# MSP_IOboard.net
KiCad netlist of a schematic drawn in Altium Designer
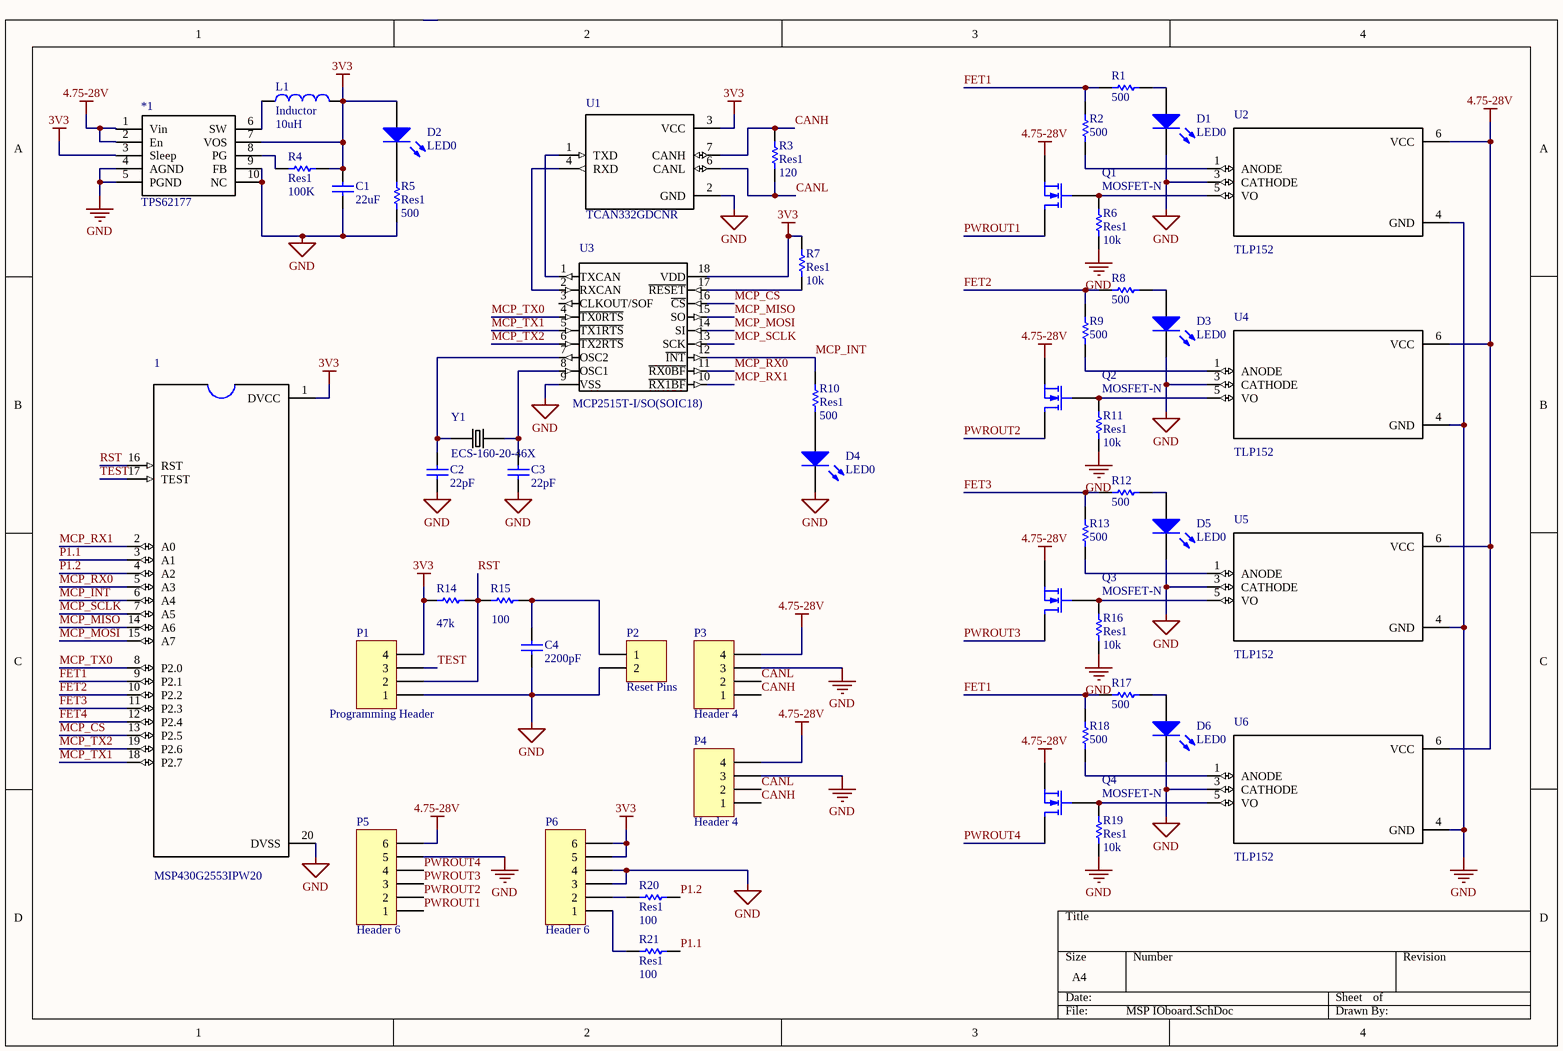
[diagram p0: MSP IOboard.SchDoc]

(export (version "E")
  (design (tool "Eeschema 10.0.6"))
  (components
    (comp (ref "*1")
      (value "TPS62177")
      (footprint "SON80P400X400X80-10N")
      (libsource (lib "SON80P400X400X80-10N") (part "TPS62177"))
    )
    (comp (ref "1")
      (value "MSP430G2553IPW20")
      (footprint "TSSOP-20")
      (description "MSP430G2x53, MSP430G2x13 Mixed Signal Microcontroller 20-TSSOP -40 to 85")
      (fields (field (name "MF") "Texas Instruments"))
      (libsource (lib "MSP430G2553IPW20") (part "MSP430G2553IPW20"))
    )
    (comp (ref "C1")
      (value "22uF")
      (footprint "0603")
      (description "Capacitor")
      (fields (field (name "Comment") "Cap") (field (name "PUBLISHER") "Altium Limited"))
      (libsource (lib "Miscellaneous Devices") (part "Cap"))
    )
    (comp (ref "C2")
      (value "22pF")
      (footprint "0603")
      (description "Capacitor")
      (fields (field (name "Comment") "Cap") (field (name "PUBLISHER") "Altium Limited"))
      (libsource (lib "Miscellaneous Devices") (part "Cap"))
    )
    (comp (ref "C3")
      (value "22pF")
      (footprint "0603")
      (description "Capacitor")
      (fields (field (name "Comment") "Cap") (field (name "PUBLISHER") "Altium Limited"))
      (libsource (lib "Miscellaneous Devices") (part "Cap"))
    )
    (comp (ref "C4")
      (value "2200pF")
      (footprint "0603")
      (description "Capacitor")
      (fields (field (name "Comment") "Cap") (field (name "PUBLISHER") "Altium Limited"))
      (libsource (lib "Miscellaneous Devices") (part "Cap"))
    )
    (comp (ref "D1")
      (value "LED0")
      (footprint "0603")
      (description "Typical INFRARED GaAs LED")
      (fields (field (name "PUBLISHER") "Altium Limited"))
      (libsource (lib "Miscellaneous Devices") (part "LED0"))
    )
    (comp (ref "D2")
      (value "LED0")
      (footprint "0603")
      (description "Typical INFRARED GaAs LED")
      (fields (field (name "PUBLISHER") "Altium Limited"))
      (libsource (lib "Miscellaneous Devices") (part "LED0"))
    )
    (comp (ref "D3")
      (value "LED0")
      (footprint "0603")
      (description "Typical INFRARED GaAs LED")
      (fields (field (name "PUBLISHER") "Altium Limited"))
      (libsource (lib "Miscellaneous Devices") (part "LED0"))
    )
    (comp (ref "D4")
      (value "LED0")
      (footprint "0603")
      (description "Typical INFRARED GaAs LED")
      (fields (field (name "PUBLISHER") "Altium Limited"))
      (libsource (lib "Miscellaneous Devices") (part "LED0"))
    )
    (comp (ref "D5")
      (value "LED0")
      (footprint "0603")
      (description "Typical INFRARED GaAs LED")
      (fields (field (name "PUBLISHER") "Altium Limited"))
      (libsource (lib "Miscellaneous Devices") (part "LED0"))
    )
    (comp (ref "D6")
      (value "LED0")
      (footprint "0603")
      (description "Typical INFRARED GaAs LED")
      (fields (field (name "PUBLISHER") "Altium Limited"))
      (libsource (lib "Miscellaneous Devices") (part "LED0"))
    )
    (comp (ref "L1")
      (value "Inductor")
      (footprint "INDC2520X18N")
      (fields (field (name "ALTIUM_VALUE") "10uH") (field (name "PUBLISHER") "Altium Limited"))
      (libsource (lib "Miscellaneous Devices") (part "Inductor"))
    )
    (comp (ref "P1")
      (value "Programming Header")
      (footprint "HDR1X4")
      (description "Header, 4-Pin")
      (fields (field (name "PUBLISHER") "Altium Limited"))
      (libsource (lib "Miscellaneous Connectors") (part "Header 4"))
    )
    (comp (ref "P2")
      (value "Reset Pins")
      (footprint "HDR1X2")
      (description "Header, 2-Pin")
      (fields (field (name "PUBLISHER") "Altium Limited"))
      (libsource (lib "Miscellaneous Connectors") (part "Header 2"))
    )
    (comp (ref "P3")
      (value "Header 4")
      (footprint "HDR1X4")
      (description "Header, 4-Pin")
      (fields (field (name "PUBLISHER") "Altium Limited"))
      (libsource (lib "Miscellaneous Connectors") (part "Header 4"))
    )
    (comp (ref "P4")
      (value "Header 4")
      (footprint "HDR1X4")
      (description "Header, 4-Pin")
      (fields (field (name "PUBLISHER") "Altium Limited"))
      (libsource (lib "Miscellaneous Connectors") (part "Header 4"))
    )
    (comp (ref "P5")
      (value "Header 6")
      (footprint "HDR1X6")
      (description "Header, 6-Pin")
      (fields (field (name "PUBLISHER") "Altium Limited"))
      (libsource (lib "Miscellaneous Connectors") (part "Header 6"))
    )
    (comp (ref "P6")
      (value "Header 6")
      (footprint "HDR1X6")
      (description "Header, 6-Pin")
      (fields (field (name "PUBLISHER") "Altium Limited"))
      (libsource (lib "Miscellaneous Connectors") (part "Header 6"))
    )
    (comp (ref "Q1")
      (value "MOSFET-N")
      (footprint "SOT95P230X110-3N")
      (description "N-Channel MOSFET")
      (fields (field (name "PUBLISHER") "Altium Limited"))
      (libsource (lib "Miscellaneous Devices") (part "MOSFET-N"))
    )
    (comp (ref "Q2")
      (value "MOSFET-N")
      (footprint "SOT95P230X110-3N")
      (description "N-Channel MOSFET")
      (fields (field (name "PUBLISHER") "Altium Limited"))
      (libsource (lib "Miscellaneous Devices") (part "MOSFET-N"))
    )
    (comp (ref "Q3")
      (value "MOSFET-N")
      (footprint "SOT95P230X110-3N")
      (description "N-Channel MOSFET")
      (fields (field (name "PUBLISHER") "Altium Limited"))
      (libsource (lib "Miscellaneous Devices") (part "MOSFET-N"))
    )
    (comp (ref "Q4")
      (value "MOSFET-N")
      (footprint "SOT95P230X110-3N")
      (description "N-Channel MOSFET")
      (fields (field (name "PUBLISHER") "Altium Limited"))
      (libsource (lib "Miscellaneous Devices") (part "MOSFET-N"))
    )
    (comp (ref "R1")
      (value "500")
      (footprint "RESC2012X70")
      (description "Resistor")
      (fields (field (name "Comment") "Res1") (field (name "PUBLISHER") "Altium Limited"))
      (libsource (lib "Miscellaneous Devices") (part "Res1"))
    )
    (comp (ref "R2")
      (value "500")
      (footprint "RESC2012X70")
      (description "Resistor")
      (fields (field (name "Comment") "Res1") (field (name "PUBLISHER") "Altium Limited"))
      (libsource (lib "Miscellaneous Devices") (part "Res1"))
    )
    (comp (ref "R3")
      (value "Res1")
      (footprint "AXIAL-0.3")
      (description "Resistor")
      (fields (field (name "ALTIUM_VALUE") "120") (field (name "PUBLISHER") "Altium Limited"))
      (libsource (lib "Miscellaneous Devices") (part "Res1"))
    )
    (comp (ref "R4")
      (value "Res1")
      (footprint "RESC2012X70")
      (description "Resistor")
      (fields (field (name "ALTIUM_VALUE") "100K") (field (name "PUBLISHER") "Altium Limited"))
      (libsource (lib "Miscellaneous Devices") (part "Res1"))
    )
    (comp (ref "R5")
      (value "Res1")
      (footprint "RESC2012X70")
      (description "Resistor")
      (fields (field (name "ALTIUM_VALUE") "500") (field (name "PUBLISHER") "Altium Limited"))
      (libsource (lib "Miscellaneous Devices") (part "Res1"))
    )
    (comp (ref "R6")
      (value "Res1")
      (footprint "RESC2012X70")
      (description "Resistor")
      (fields (field (name "ALTIUM_VALUE") "10k") (field (name "PUBLISHER") "Altium Limited"))
      (libsource (lib "Miscellaneous Devices") (part "Res1"))
    )
    (comp (ref "R7")
      (value "Res1")
      (footprint "RESC2012X70")
      (description "Resistor")
      (fields (field (name "ALTIUM_VALUE") "10k") (field (name "PUBLISHER") "Altium Limited"))
      (libsource (lib "Miscellaneous Devices") (part "Res1"))
    )
    (comp (ref "R8")
      (value "500")
      (footprint "RESC2012X70")
      (description "Resistor")
      (fields (field (name "Comment") "Res1") (field (name "PUBLISHER") "Altium Limited"))
      (libsource (lib "Miscellaneous Devices") (part "Res1"))
    )
    (comp (ref "R9")
      (value "500")
      (footprint "RESC2012X70")
      (description "Resistor")
      (fields (field (name "Comment") "Res1") (field (name "PUBLISHER") "Altium Limited"))
      (libsource (lib "Miscellaneous Devices") (part "Res1"))
    )
    (comp (ref "R10")
      (value "Res1")
      (footprint "RESC2012X70")
      (description "Resistor")
      (fields (field (name "ALTIUM_VALUE") "500") (field (name "PUBLISHER") "Altium Limited"))
      (libsource (lib "Miscellaneous Devices") (part "Res1"))
    )
    (comp (ref "R11")
      (value "Res1")
      (footprint "RESC2012X70")
      (description "Resistor")
      (fields (field (name "ALTIUM_VALUE") "10k") (field (name "PUBLISHER") "Altium Limited"))
      (libsource (lib "Miscellaneous Devices") (part "Res1"))
    )
    (comp (ref "R12")
      (value "500")
      (footprint "RESC2012X70")
      (description "Resistor")
      (fields (field (name "Comment") "Res1") (field (name "PUBLISHER") "Altium Limited"))
      (libsource (lib "Miscellaneous Devices") (part "Res1"))
    )
    (comp (ref "R13")
      (value "500")
      (footprint "RESC2012X70")
      (description "Resistor")
      (fields (field (name "Comment") "Res1") (field (name "PUBLISHER") "Altium Limited"))
      (libsource (lib "Miscellaneous Devices") (part "Res1"))
    )
    (comp (ref "R14")
      (value "47k")
      (footprint "RESC2012X70")
      (description "Resistor")
      (fields (field (name "Comment") "Res1") (field (name "PUBLISHER") "Altium Limited"))
      (libsource (lib "Miscellaneous Devices") (part "Res1"))
    )
    (comp (ref "R15")
      (value "100")
      (footprint "RESC2012X70")
      (description "Resistor")
      (fields (field (name "Comment") "Res1") (field (name "PUBLISHER") "Altium Limited"))
      (libsource (lib "Miscellaneous Devices") (part "Res1"))
    )
    (comp (ref "R16")
      (value "Res1")
      (footprint "RESC2012X70")
      (description "Resistor")
      (fields (field (name "ALTIUM_VALUE") "10k") (field (name "PUBLISHER") "Altium Limited"))
      (libsource (lib "Miscellaneous Devices") (part "Res1"))
    )
    (comp (ref "R17")
      (value "500")
      (footprint "RESC2012X70")
      (description "Resistor")
      (fields (field (name "Comment") "Res1") (field (name "PUBLISHER") "Altium Limited"))
      (libsource (lib "Miscellaneous Devices") (part "Res1"))
    )
    (comp (ref "R18")
      (value "500")
      (footprint "RESC2012X70")
      (description "Resistor")
      (fields (field (name "Comment") "Res1") (field (name "PUBLISHER") "Altium Limited"))
      (libsource (lib "Miscellaneous Devices") (part "Res1"))
    )
    (comp (ref "R19")
      (value "Res1")
      (footprint "RESC2012X70")
      (description "Resistor")
      (fields (field (name "ALTIUM_VALUE") "10k") (field (name "PUBLISHER") "Altium Limited"))
      (libsource (lib "Miscellaneous Devices") (part "Res1"))
    )
    (comp (ref "R20")
      (value "Res1")
      (footprint "RESC2012X70")
      (description "Resistor")
      (fields (field (name "ALTIUM_VALUE") "100") (field (name "PUBLISHER") "Altium Limited"))
      (libsource (lib "Miscellaneous Devices") (part "Res1"))
    )
    (comp (ref "R21")
      (value "Res1")
      (footprint "RESC2012X70")
      (description "Resistor")
      (fields (field (name "ALTIUM_VALUE") "100") (field (name "PUBLISHER") "Altium Limited"))
      (libsource (lib "Miscellaneous Devices") (part "Res1"))
    )
    (comp (ref "U1")
      (value "TCAN332GDCNR")
      (footprint "SOT65P280X145-8N")
      (description "3.3-V CAN Transceivers with CAN FD _Flexible Data Rate_ 8-SOT-23 -40 to 125")
      (fields (field (name "MF") "Texas Instruments"))
      (libsource (lib "TCAN332GDCNR") (part "TCAN332GDCNR"))
    )
    (comp (ref "U2")
      (value "TLP152")
      (footprint "SOIC127P375X700X220-5N")
      (description "Optocoupler, Gate Driver, 3.75kv, Smdip")
      (fields (field (name "MF") "Toshiba"))
      (libsource (lib "TLP152") (part "TLP152"))
    )
    (comp (ref "U3")
      (value "MCP2515T-I/SO(SOIC18)")
      (footprint "SOIC18-1.27-11.5X7.5MM")
      (description "MCP2515 Series 5.5 V 1 Mb/s Stand Alone SPI Interface CAN Controller- SOIC-18")
      (fields (field (name "MF") "Microchip") (field (name "MP") "MCP2515T-I/SO"))
      (libsource (lib "INTERFACE-MCP2515T-I_SO_SOIC18_") (part "INTERFACE-MCP2515T-I/SO(SOIC18)"))
    )
    (comp (ref "U4")
      (value "TLP152")
      (footprint "SOIC127P375X700X220-5N")
      (description "Optocoupler, Gate Driver, 3.75kv, Smdip")
      (fields (field (name "MF") "Toshiba"))
      (libsource (lib "TLP152") (part "TLP152"))
    )
    (comp (ref "U5")
      (value "TLP152")
      (footprint "SOIC127P375X700X220-5N")
      (description "Optocoupler, Gate Driver, 3.75kv, Smdip")
      (fields (field (name "MF") "Toshiba"))
      (libsource (lib "TLP152") (part "TLP152"))
    )
    (comp (ref "U6")
      (value "TLP152")
      (footprint "SOIC127P375X700X220-5N")
      (description "Optocoupler, Gate Driver, 3.75kv, Smdip")
      (fields (field (name "MF") "Toshiba"))
      (libsource (lib "TLP152") (part "TLP152"))
    )
    (comp (ref "Y1")
      (value "ECS-160-20-46X")
      (footprint "XTAL_ECS-160-20-46X")
      (description "Crystal 16MHz Â±30ppm _Tol_ Â±50ppm _Stability_ 20pF FUND 50Ohm")
      (fields (field (name "MF") "ECS Inc."))
      (libsource (lib "ECS-160-20-46X") (part "ECS-160-20-46X"))
    )
  )
  (nets
    (net (code "1") (name "/CANH") (class "Default")
      (node (ref "P3") (pin "1") (pinfunction "1_1") (pintype "passive"))
      (node (ref "P4") (pin "1") (pinfunction "1_1") (pintype "passive"))
      (node (ref "R3") (pin "2") (pinfunction "2_2") (pintype "passive"))
      (node (ref "U1") (pin "7") (pinfunction "CANH_7") (pintype "bidirectional"))
    )
    (net (code "2") (name "/CANL") (class "Default")
      (node (ref "P3") (pin "2") (pinfunction "2_2") (pintype "passive"))
      (node (ref "P4") (pin "2") (pinfunction "2_2") (pintype "passive"))
      (node (ref "R3") (pin "1") (pinfunction "1_1") (pintype "passive"))
      (node (ref "U1") (pin "6") (pinfunction "CANL_6") (pintype "bidirectional"))
    )
    (net (code "3") (name "/FET1") (class "Default")
      (node (ref "1") (pin "9") (pinfunction "P2.1_9") (pintype "bidirectional"))
      (node (ref "R1") (pin "1") (pinfunction "1_1") (pintype "passive"))
      (node (ref "R17") (pin "2") (pinfunction "2_2") (pintype "passive"))
      (node (ref "R18") (pin "1") (pinfunction "1_1") (pintype "passive"))
      (node (ref "R2") (pin "2") (pinfunction "2_2") (pintype "passive"))
    )
    (net (code "4") (name "/FET2") (class "Default")
      (node (ref "1") (pin "10") (pinfunction "P2.2_10") (pintype "bidirectional"))
      (node (ref "R8") (pin "1") (pinfunction "1_1") (pintype "passive"))
      (node (ref "R9") (pin "1") (pinfunction "1_1") (pintype "passive"))
    )
    (net (code "5") (name "/FET3") (class "Default")
      (node (ref "1") (pin "11") (pinfunction "P2.3_11") (pintype "bidirectional"))
      (node (ref "R12") (pin "2") (pinfunction "2_2") (pintype "passive"))
      (node (ref "R13") (pin "1") (pinfunction "1_1") (pintype "passive"))
    )
    (net (code "6") (name "/FET4") (class "Default")
      (node (ref "1") (pin "12") (pinfunction "P2.4_12") (pintype "bidirectional"))
    )
    (net (code "7") (name "/MCP_CS") (class "Default")
      (node (ref "1") (pin "13") (pinfunction "P2.5_13") (pintype "bidirectional"))
      (node (ref "U3") (pin "16") (pinfunction "~{CS}_16") (pintype "input"))
    )
    (net (code "8") (name "/MCP_INT") (class "Default")
      (node (ref "1") (pin "6") (pinfunction "A4_6") (pintype "bidirectional"))
      (node (ref "R10") (pin "2") (pinfunction "2_2") (pintype "passive"))
      (node (ref "U3") (pin "12") (pinfunction "~{INT}_12") (pintype "output"))
    )
    (net (code "9") (name "/MCP_MISO") (class "Default")
      (node (ref "1") (pin "14") (pinfunction "A6_14") (pintype "bidirectional"))
      (node (ref "U3") (pin "15") (pinfunction "SO_15") (pintype "output"))
    )
    (net (code "10") (name "/MCP_MOSI") (class "Default")
      (node (ref "1") (pin "15") (pinfunction "A7_15") (pintype "bidirectional"))
      (node (ref "U3") (pin "14") (pinfunction "SI_14") (pintype "input"))
    )
    (net (code "11") (name "/MCP_RX0") (class "Default")
      (node (ref "1") (pin "5") (pinfunction "A3_5") (pintype "bidirectional"))
      (node (ref "U3") (pin "11") (pinfunction "~{RX0BF}_11") (pintype "output"))
    )
    (net (code "12") (name "/MCP_RX1") (class "Default")
      (node (ref "1") (pin "2") (pinfunction "A0_2") (pintype "bidirectional"))
      (node (ref "U3") (pin "10") (pinfunction "~{RX1BF}_10") (pintype "output"))
    )
    (net (code "13") (name "/MCP_SCLK") (class "Default")
      (node (ref "1") (pin "7") (pinfunction "A5_7") (pintype "bidirectional"))
      (node (ref "U3") (pin "13") (pinfunction "SCK_13") (pintype "input"))
    )
    (net (code "14") (name "/MCP_TX0") (class "Default")
      (node (ref "1") (pin "8") (pinfunction "P2.0_8") (pintype "bidirectional"))
      (node (ref "U3") (pin "4") (pinfunction "~{TX0RTS}_4") (pintype "input"))
    )
    (net (code "15") (name "/MCP_TX1") (class "Default")
      (node (ref "1") (pin "18") (pinfunction "P2.7_18") (pintype "bidirectional"))
      (node (ref "U3") (pin "5") (pinfunction "~{TX1RTS}_5") (pintype "input"))
    )
    (net (code "16") (name "/MCP_TX2") (class "Default")
      (node (ref "1") (pin "19") (pinfunction "P2.6_19") (pintype "bidirectional"))
      (node (ref "U3") (pin "6") (pinfunction "~{TX2RTS}_6") (pintype "input"))
    )
    (net (code "17") (name "/P1.1") (class "Default")
      (node (ref "1") (pin "3") (pinfunction "A1_3") (pintype "bidirectional"))
      (node (ref "R21") (pin "1") (pinfunction "1_1") (pintype "passive"))
    )
    (net (code "18") (name "/P1.2") (class "Default")
      (node (ref "1") (pin "4") (pinfunction "A2_4") (pintype "bidirectional"))
      (node (ref "R20") (pin "1") (pinfunction "1_1") (pintype "passive"))
    )
    (net (code "19") (name "/PWROUT1") (class "Default")
      (node (ref "P5") (pin "1") (pinfunction "1_1") (pintype "passive"))
      (node (ref "Q1") (pin "1") (pinfunction "D_1") (pintype "passive"))
    )
    (net (code "20") (name "/PWROUT2") (class "Default")
      (node (ref "P5") (pin "2") (pinfunction "2_2") (pintype "passive"))
      (node (ref "Q2") (pin "1") (pinfunction "D_1") (pintype "passive"))
    )
    (net (code "21") (name "/PWROUT3") (class "Default")
      (node (ref "P5") (pin "3") (pinfunction "3_3") (pintype "passive"))
      (node (ref "Q3") (pin "1") (pinfunction "D_1") (pintype "passive"))
    )
    (net (code "22") (name "/PWROUT4") (class "Default")
      (node (ref "P5") (pin "4") (pinfunction "4_4") (pintype "passive"))
      (node (ref "Q4") (pin "1") (pinfunction "D_1") (pintype "passive"))
    )
    (net (code "23") (name "/RST") (class "Default")
      (node (ref "1") (pin "16") (pinfunction "RST_16") (pintype "input"))
      (node (ref "P1") (pin "2") (pinfunction "2_2") (pintype "passive"))
      (node (ref "R14") (pin "2") (pinfunction "2_2") (pintype "passive"))
      (node (ref "R15") (pin "1") (pinfunction "1_1") (pintype "passive"))
    )
    (net (code "24") (name "/TEST") (class "Default")
      (node (ref "1") (pin "17") (pinfunction "TEST_17") (pintype "input"))
      (node (ref "P1") (pin "3") (pinfunction "3_3") (pintype "passive"))
    )
    (net (code "25") (name "3V3") (class "Default")
      (node (ref "*1") (pin "3") (pinfunction "Sleep_3") (pintype "passive"))
      (node (ref "*1") (pin "7") (pinfunction "VOS_7") (pintype "passive"))
      (node (ref "1") (pin "1") (pinfunction "DVCC_1") (pintype "power_in"))
      (node (ref "C1") (pin "2") (pinfunction "2_2") (pintype "passive"))
      (node (ref "D2") (pin "1") (pinfunction "A_1") (pintype "passive"))
      (node (ref "L1") (pin "2") (pinfunction "2_2") (pintype "passive"))
      (node (ref "P1") (pin "4") (pinfunction "4_4") (pintype "passive"))
      (node (ref "P6") (pin "5") (pinfunction "5_5") (pintype "passive"))
      (node (ref "P6") (pin "6") (pinfunction "6_6") (pintype "passive"))
      (node (ref "R14") (pin "1") (pinfunction "1_1") (pintype "passive"))
      (node (ref "R4") (pin "1") (pinfunction "1_1") (pintype "passive"))
      (node (ref "R7") (pin "2") (pinfunction "2_2") (pintype "passive"))
      (node (ref "U1") (pin "3") (pinfunction "VCC_3") (pintype "power_in"))
      (node (ref "U3") (pin "18") (pinfunction "VDD_18") (pintype "power_in"))
    )
    (net (code "26") (name "4.75-28V") (class "Default")
      (node (ref "*1") (pin "1") (pinfunction "Vin_1") (pintype "passive"))
      (node (ref "*1") (pin "2") (pinfunction "En_2") (pintype "passive"))
      (node (ref "P3") (pin "4") (pinfunction "4_4") (pintype "passive"))
      (node (ref "P4") (pin "4") (pinfunction "4_4") (pintype "passive"))
      (node (ref "P5") (pin "6") (pinfunction "6_6") (pintype "passive"))
      (node (ref "Q1") (pin "3") (pinfunction "S_3") (pintype "passive"))
      (node (ref "Q2") (pin "3") (pinfunction "S_3") (pintype "passive"))
      (node (ref "Q3") (pin "3") (pinfunction "S_3") (pintype "passive"))
      (node (ref "Q4") (pin "3") (pinfunction "S_3") (pintype "passive"))
      (node (ref "U2") (pin "6") (pinfunction "VCC_6") (pintype "power_in"))
      (node (ref "U4") (pin "6") (pinfunction "VCC_6") (pintype "power_in"))
      (node (ref "U5") (pin "6") (pinfunction "VCC_6") (pintype "power_in"))
      (node (ref "U6") (pin "6") (pinfunction "VCC_6") (pintype "power_in"))
    )
    (net (code "27") (name "GND") (class "Default")
      (node (ref "*1") (pin "10") (pinfunction "NC_10") (pintype "passive"))
      (node (ref "*1") (pin "4") (pinfunction "AGND_4") (pintype "passive"))
      (node (ref "*1") (pin "5") (pinfunction "PGND_5") (pintype "passive"))
      (node (ref "*1") (pin "9") (pinfunction "FB_9") (pintype "passive"))
      (node (ref "1") (pin "20") (pinfunction "DVSS_20") (pintype "passive"))
      (node (ref "C1") (pin "1") (pinfunction "1_1") (pintype "passive"))
      (node (ref "C2") (pin "1") (pinfunction "1_1") (pintype "passive"))
      (node (ref "C3") (pin "1") (pinfunction "1_1") (pintype "passive"))
      (node (ref "C4") (pin "1") (pinfunction "1_1") (pintype "passive"))
      (node (ref "D1") (pin "2") (pinfunction "K_2") (pintype "passive"))
      (node (ref "D3") (pin "2") (pinfunction "K_2") (pintype "passive"))
      (node (ref "D4") (pin "2") (pinfunction "K_2") (pintype "passive"))
      (node (ref "D5") (pin "2") (pinfunction "K_2") (pintype "passive"))
      (node (ref "D6") (pin "2") (pinfunction "K_2") (pintype "passive"))
      (node (ref "P1") (pin "1") (pinfunction "1_1") (pintype "passive"))
      (node (ref "P2") (pin "2") (pinfunction "2_2") (pintype "passive"))
      (node (ref "P3") (pin "3") (pinfunction "3_3") (pintype "passive"))
      (node (ref "P4") (pin "3") (pinfunction "3_3") (pintype "passive"))
      (node (ref "P5") (pin "5") (pinfunction "5_5") (pintype "passive"))
      (node (ref "P6") (pin "3") (pinfunction "3_3") (pintype "passive"))
      (node (ref "P6") (pin "4") (pinfunction "4_4") (pintype "passive"))
      (node (ref "R11") (pin "1") (pinfunction "1_1") (pintype "passive"))
      (node (ref "R16") (pin "1") (pinfunction "1_1") (pintype "passive"))
      (node (ref "R19") (pin "1") (pinfunction "1_1") (pintype "passive"))
      (node (ref "R5") (pin "2") (pinfunction "2_2") (pintype "passive"))
      (node (ref "R6") (pin "1") (pinfunction "1_1") (pintype "passive"))
      (node (ref "U1") (pin "2") (pinfunction "GND_2") (pintype "power_in"))
      (node (ref "U2") (pin "3") (pinfunction "CATHODE_3") (pintype "bidirectional"))
      (node (ref "U2") (pin "4") (pinfunction "GND_4") (pintype "power_in"))
      (node (ref "U3") (pin "9") (pinfunction "VSS_9") (pintype "power_in"))
      (node (ref "U4") (pin "3") (pinfunction "CATHODE_3") (pintype "bidirectional"))
      (node (ref "U4") (pin "4") (pinfunction "GND_4") (pintype "power_in"))
      (node (ref "U5") (pin "3") (pinfunction "CATHODE_3") (pintype "bidirectional"))
      (node (ref "U5") (pin "4") (pinfunction "GND_4") (pintype "power_in"))
      (node (ref "U6") (pin "3") (pinfunction "CATHODE_3") (pintype "bidirectional"))
      (node (ref "U6") (pin "4") (pinfunction "GND_4") (pintype "power_in"))
    )
    (net (code "28") (name "Net-(*1-PG)") (class "Default")
      (node (ref "*1") (pin "8") (pinfunction "PG_8") (pintype "passive"))
      (node (ref "R4") (pin "2") (pinfunction "2_2") (pintype "passive"))
    )
    (net (code "29") (name "Net-(*1-SW)") (class "Default")
      (node (ref "*1") (pin "6") (pinfunction "SW_6") (pintype "passive"))
      (node (ref "L1") (pin "1") (pinfunction "1_1") (pintype "passive"))
    )
    (net (code "30") (name "Net-(C4-Pad2)") (class "Default")
      (node (ref "C4") (pin "2") (pinfunction "2_2") (pintype "passive"))
      (node (ref "P2") (pin "1") (pinfunction "1_1") (pintype "passive"))
      (node (ref "R15") (pin "2") (pinfunction "2_2") (pintype "passive"))
    )
    (net (code "31") (name "Net-(D1-A)") (class "Default")
      (node (ref "D1") (pin "1") (pinfunction "A_1") (pintype "passive"))
      (node (ref "R1") (pin "2") (pinfunction "2_2") (pintype "passive"))
    )
    (net (code "32") (name "Net-(D2-K)") (class "Default")
      (node (ref "D2") (pin "2") (pinfunction "K_2") (pintype "passive"))
      (node (ref "R5") (pin "1") (pinfunction "1_1") (pintype "passive"))
    )
    (net (code "33") (name "Net-(D3-A)") (class "Default")
      (node (ref "D3") (pin "1") (pinfunction "A_1") (pintype "passive"))
      (node (ref "R8") (pin "2") (pinfunction "2_2") (pintype "passive"))
    )
    (net (code "34") (name "Net-(D4-A)") (class "Default")
      (node (ref "D4") (pin "1") (pinfunction "A_1") (pintype "passive"))
      (node (ref "R10") (pin "1") (pinfunction "1_1") (pintype "passive"))
    )
    (net (code "35") (name "Net-(D5-A)") (class "Default")
      (node (ref "D5") (pin "1") (pinfunction "A_1") (pintype "passive"))
      (node (ref "R12") (pin "1") (pinfunction "1_1") (pintype "passive"))
    )
    (net (code "36") (name "Net-(D6-A)") (class "Default")
      (node (ref "D6") (pin "1") (pinfunction "A_1") (pintype "passive"))
      (node (ref "R17") (pin "1") (pinfunction "1_1") (pintype "passive"))
    )
    (net (code "37") (name "Net-(P6-Pad1)") (class "Default")
      (node (ref "P6") (pin "1") (pinfunction "1_1") (pintype "passive"))
      (node (ref "R21") (pin "2") (pinfunction "2_2") (pintype "passive"))
    )
    (net (code "38") (name "Net-(P6-Pad2)") (class "Default")
      (node (ref "P6") (pin "2") (pinfunction "2_2") (pintype "passive"))
      (node (ref "R20") (pin "2") (pinfunction "2_2") (pintype "passive"))
    )
    (net (code "39") (name "Net-(Q1-G)") (class "Default")
      (node (ref "Q1") (pin "2") (pinfunction "G_2") (pintype "passive"))
      (node (ref "R6") (pin "2") (pinfunction "2_2") (pintype "passive"))
      (node (ref "U2") (pin "5") (pinfunction "VO_5") (pintype "bidirectional"))
    )
    (net (code "40") (name "Net-(Q2-G)") (class "Default")
      (node (ref "Q2") (pin "2") (pinfunction "G_2") (pintype "passive"))
      (node (ref "R11") (pin "2") (pinfunction "2_2") (pintype "passive"))
      (node (ref "U4") (pin "5") (pinfunction "VO_5") (pintype "bidirectional"))
    )
    (net (code "41") (name "Net-(Q3-G)") (class "Default")
      (node (ref "Q3") (pin "2") (pinfunction "G_2") (pintype "passive"))
      (node (ref "R16") (pin "2") (pinfunction "2_2") (pintype "passive"))
      (node (ref "U5") (pin "5") (pinfunction "VO_5") (pintype "bidirectional"))
    )
    (net (code "42") (name "Net-(Q4-G)") (class "Default")
      (node (ref "Q4") (pin "2") (pinfunction "G_2") (pintype "passive"))
      (node (ref "R19") (pin "2") (pinfunction "2_2") (pintype "passive"))
      (node (ref "U6") (pin "5") (pinfunction "VO_5") (pintype "bidirectional"))
    )
    (net (code "43") (name "Net-(U1-RXD)") (class "Default")
      (node (ref "U1") (pin "4") (pinfunction "RXD_4") (pintype "output"))
      (node (ref "U3") (pin "2") (pinfunction "RXCAN_2") (pintype "input"))
    )
    (net (code "44") (name "Net-(U1-TXD)") (class "Default")
      (node (ref "U1") (pin "1") (pinfunction "TXD_1") (pintype "input"))
      (node (ref "U3") (pin "1") (pinfunction "TXCAN_1") (pintype "output"))
    )
    (net (code "45") (name "Net-(U2-ANODE)") (class "Default")
      (node (ref "R2") (pin "1") (pinfunction "1_1") (pintype "passive"))
      (node (ref "U2") (pin "1") (pinfunction "ANODE_1") (pintype "bidirectional"))
    )
    (net (code "46") (name "Net-(U3-OSC1)") (class "Default")
      (node (ref "C3") (pin "2") (pinfunction "2_2") (pintype "passive"))
      (node (ref "U3") (pin "8") (pinfunction "OSC1_8") (pintype "input"))
      (node (ref "Y1") (pin "2") (pinfunction "2_2") (pintype "passive"))
    )
    (net (code "47") (name "Net-(U3-OSC2)") (class "Default")
      (node (ref "C2") (pin "2") (pinfunction "2_2") (pintype "passive"))
      (node (ref "U3") (pin "7") (pinfunction "OSC2_7") (pintype "output"))
      (node (ref "Y1") (pin "1") (pinfunction "1_1") (pintype "passive"))
    )
    (net (code "48") (name "Net-(U3-~{RESET})") (class "Default")
      (node (ref "R7") (pin "1") (pinfunction "1_1") (pintype "passive"))
      (node (ref "U3") (pin "17") (pinfunction "~{RESET}_17") (pintype "input"))
    )
    (net (code "49") (name "Net-(U4-ANODE)") (class "Default")
      (node (ref "R9") (pin "2") (pinfunction "2_2") (pintype "passive"))
      (node (ref "U4") (pin "1") (pinfunction "ANODE_1") (pintype "bidirectional"))
    )
    (net (code "50") (name "Net-(U5-ANODE)") (class "Default")
      (node (ref "R13") (pin "2") (pinfunction "2_2") (pintype "passive"))
      (node (ref "U5") (pin "1") (pinfunction "ANODE_1") (pintype "bidirectional"))
    )
    (net (code "51") (name "Net-(U6-ANODE)") (class "Default")
      (node (ref "R18") (pin "2") (pinfunction "2_2") (pintype "passive"))
      (node (ref "U6") (pin "1") (pinfunction "ANODE_1") (pintype "bidirectional"))
    )
    (net (code "52") (name "unconnected-(U3-CLKOUT{slash}SOF-Pad3)") (class "Default")
      (node (ref "U3") (pin "3") (pinfunction "CLKOUT/SOF_3") (pintype "output"))
    )
  )
)
